# DRV8305.net
KiCad netlist of a schematic drawn in Altium Designer
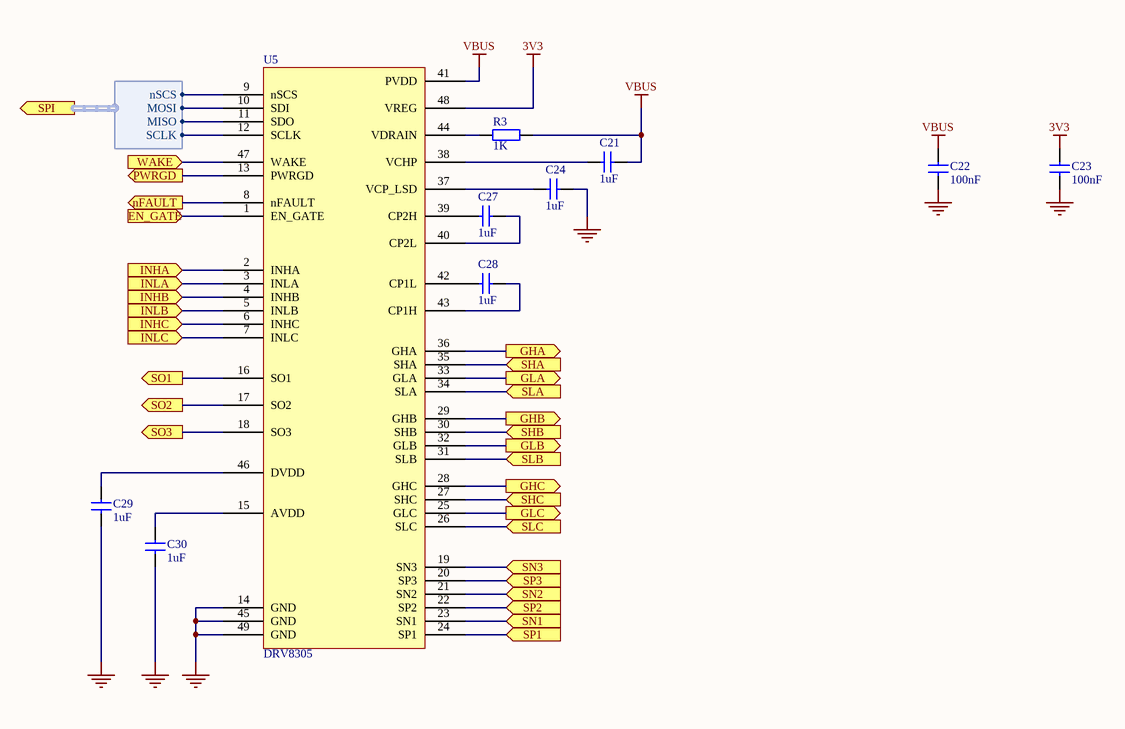
[diagram p0: DRV8305.SchDoc]

(export (version "E")
  (design (tool "Eeschema 10.0.6"))
  (components
    (comp (ref "C21")
      (value "1uF")
      (footprint "CAP0402(1005)_N")
      (description "Capacitor")
      (fields (field (name "PART") "cap_generic"))
      (libsource (lib "hitiqlib") (part "cap"))
    )
    (comp (ref "C22")
      (value "100nF")
      (footprint "CAP0402(1005)_N")
      (description "Capacitor")
      (fields (field (name "PART") "cap_generic"))
      (libsource (lib "hitiqlib") (part "cap"))
    )
    (comp (ref "C23")
      (value "100nF")
      (footprint "CAP0402(1005)_N")
      (description "Capacitor")
      (fields (field (name "PART") "cap_generic"))
      (libsource (lib "hitiqlib") (part "cap"))
    )
    (comp (ref "C24")
      (value "1uF")
      (footprint "CAP0402(1005)_N")
      (description "Capacitor")
      (fields (field (name "PART") "cap_generic"))
      (libsource (lib "hitiqlib") (part "cap"))
    )
    (comp (ref "C27")
      (value "1uF")
      (footprint "CAP0402(1005)_N")
      (description "Capacitor")
      (fields (field (name "PART") "cap_generic"))
      (libsource (lib "hitiqlib") (part "cap"))
    )
    (comp (ref "C28")
      (value "1uF")
      (footprint "CAP0402(1005)_N")
      (description "Capacitor")
      (fields (field (name "PART") "cap_generic"))
      (libsource (lib "hitiqlib") (part "cap"))
    )
    (comp (ref "C29")
      (value "1uF")
      (footprint "CAP0402(1005)_N")
      (description "Capacitor")
      (fields (field (name "PART") "cap_generic"))
      (libsource (lib "hitiqlib") (part "cap"))
    )
    (comp (ref "C30")
      (value "1uF")
      (footprint "CAP0402(1005)_N")
      (description "Capacitor")
      (fields (field (name "PART") "cap_generic"))
      (libsource (lib "hitiqlib") (part "cap"))
    )
    (comp (ref "R3")
      (value "1K")
      (footprint "RESC0603(1608)_N")
      (description "Resistor")
      (fields (field (name "PART") "res_0603"))
      (libsource (lib "hitiqlib") (part "Resistor"))
    )
    (comp (ref "U5")
      (value "DRV8305")
      (footprint "S-PQFP-G48")
      (fields (field (name "MANUFACTURER") "Texas Instruments"))
      (libsource (lib "hitiqlib") (part "DRV8305"))
    )
  )
  (nets
    (net (code "2") (name "/EN_GATE") (class "Default")
      (node (ref "U5") (pin "1") (pinfunction "EN_GATE_1") (pintype "passive"))
    )
    (net (code "3") (name "/GHA") (class "Default")
      (node (ref "U5") (pin "36") (pinfunction "GHA_36") (pintype "passive"))
    )
    (net (code "4") (name "/GHB") (class "Default")
      (node (ref "U5") (pin "29") (pinfunction "GHB_29") (pintype "passive"))
    )
    (net (code "5") (name "/GHC") (class "Default")
      (node (ref "U5") (pin "28") (pinfunction "GHC_28") (pintype "passive"))
    )
    (net (code "6") (name "/GLA") (class "Default")
      (node (ref "U5") (pin "33") (pinfunction "GLA_33") (pintype "passive"))
    )
    (net (code "7") (name "/GLB") (class "Default")
      (node (ref "U5") (pin "32") (pinfunction "GLB_32") (pintype "passive"))
    )
    (net (code "8") (name "/GLC") (class "Default")
      (node (ref "U5") (pin "25") (pinfunction "GLC_25") (pintype "passive"))
    )
    (net (code "9") (name "/INHA") (class "Default")
      (node (ref "U5") (pin "2") (pinfunction "INHA_2") (pintype "passive"))
    )
    (net (code "10") (name "/INHB") (class "Default")
      (node (ref "U5") (pin "4") (pinfunction "INHB_4") (pintype "passive"))
    )
    (net (code "11") (name "/INHC") (class "Default")
      (node (ref "U5") (pin "6") (pinfunction "INHC_6") (pintype "passive"))
    )
    (net (code "12") (name "/INLA") (class "Default")
      (node (ref "U5") (pin "3") (pinfunction "INLA_3") (pintype "passive"))
    )
    (net (code "13") (name "/INLB") (class "Default")
      (node (ref "U5") (pin "5") (pinfunction "INLB_5") (pintype "passive"))
    )
    (net (code "14") (name "/INLC") (class "Default")
      (node (ref "U5") (pin "7") (pinfunction "INLC_7") (pintype "passive"))
    )
    (net (code "15") (name "/MISO") (class "Default")
      (node (ref "U5") (pin "11") (pinfunction "SDO_11") (pintype "passive"))
    )
    (net (code "16") (name "/MOSI") (class "Default")
      (node (ref "U5") (pin "10") (pinfunction "SDI_10") (pintype "passive"))
    )
    (net (code "17") (name "/PWRGD") (class "Default")
      (node (ref "U5") (pin "13") (pinfunction "PWRGD_13") (pintype "passive"))
    )
    (net (code "18") (name "/SCLK") (class "Default")
      (node (ref "U5") (pin "12") (pinfunction "SCLK_12") (pintype "passive"))
    )
    (net (code "19") (name "/SHA") (class "Default")
      (node (ref "U5") (pin "35") (pinfunction "SHA_35") (pintype "passive"))
    )
    (net (code "20") (name "/SHB") (class "Default")
      (node (ref "U5") (pin "30") (pinfunction "SHB_30") (pintype "passive"))
    )
    (net (code "21") (name "/SHC") (class "Default")
      (node (ref "U5") (pin "27") (pinfunction "SHC_27") (pintype "passive"))
    )
    (net (code "22") (name "/SLA") (class "Default")
      (node (ref "U5") (pin "34") (pinfunction "SLA_34") (pintype "passive"))
    )
    (net (code "23") (name "/SLB") (class "Default")
      (node (ref "U5") (pin "31") (pinfunction "SLB_31") (pintype "passive"))
    )
    (net (code "24") (name "/SLC") (class "Default")
      (node (ref "U5") (pin "26") (pinfunction "SLC_26") (pintype "passive"))
    )
    (net (code "25") (name "/SN1") (class "Default")
      (node (ref "U5") (pin "23") (pinfunction "SN1_23") (pintype "passive"))
    )
    (net (code "26") (name "/SN2") (class "Default")
      (node (ref "U5") (pin "21") (pinfunction "SN2_21") (pintype "passive"))
    )
    (net (code "27") (name "/SN3") (class "Default")
      (node (ref "U5") (pin "19") (pinfunction "SN3_19") (pintype "passive"))
    )
    (net (code "28") (name "/SO1") (class "Default")
      (node (ref "U5") (pin "16") (pinfunction "SO1_16") (pintype "passive"))
    )
    (net (code "29") (name "/SO2") (class "Default")
      (node (ref "U5") (pin "17") (pinfunction "SO2_17") (pintype "passive"))
    )
    (net (code "30") (name "/SO3") (class "Default")
      (node (ref "U5") (pin "18") (pinfunction "SO3_18") (pintype "passive"))
    )
    (net (code "31") (name "/SP1") (class "Default")
      (node (ref "U5") (pin "24") (pinfunction "SP1_24") (pintype "passive"))
    )
    (net (code "32") (name "/SP2") (class "Default")
      (node (ref "U5") (pin "22") (pinfunction "SP2_22") (pintype "passive"))
    )
    (net (code "33") (name "/SP3") (class "Default")
      (node (ref "U5") (pin "20") (pinfunction "SP3_20") (pintype "passive"))
    )
    (net (code "34") (name "/WAKE") (class "Default")
      (node (ref "U5") (pin "47") (pinfunction "WAKE_47") (pintype "passive"))
    )
    (net (code "35") (name "/nFAULT") (class "Default")
      (node (ref "U5") (pin "8") (pinfunction "nFAULT_8") (pintype "passive"))
    )
    (net (code "36") (name "/nSCS") (class "Default")
      (node (ref "U5") (pin "9") (pinfunction "nSCS_9") (pintype "passive"))
    )
    (net (code "38") (name "3V3") (class "Default")
      (node (ref "C23") (pin "2") (pintype "passive"))
      (node (ref "U5") (pin "48") (pinfunction "VREG_48") (pintype "passive"))
    )
    (net (code "39") (name "GND") (class "Default")
      (node (ref "C22") (pin "1") (pintype "passive"))
      (node (ref "C23") (pin "1") (pintype "passive"))
      (node (ref "C24") (pin "1") (pintype "passive"))
      (node (ref "C29") (pin "1") (pintype "passive"))
      (node (ref "C30") (pin "1") (pintype "passive"))
      (node (ref "U5") (pin "14") (pinfunction "GND_14") (pintype "passive"))
      (node (ref "U5") (pin "45") (pinfunction "GND_45") (pintype "passive"))
      (node (ref "U5") (pin "49") (pinfunction "GND_49") (pintype "passive"))
    )
    (net (code "40") (name "Net-(U5-AVDD)") (class "Default")
      (node (ref "C30") (pin "2") (pintype "passive"))
      (node (ref "U5") (pin "15") (pinfunction "AVDD_15") (pintype "passive"))
    )
    (net (code "41") (name "Net-(U5-CP1H)") (class "Default")
      (node (ref "C28") (pin "1") (pintype "passive"))
      (node (ref "U5") (pin "43") (pinfunction "CP1H_43") (pintype "passive"))
    )
    (net (code "42") (name "Net-(U5-CP1L)") (class "Default")
      (node (ref "C28") (pin "2") (pintype "passive"))
      (node (ref "U5") (pin "42") (pinfunction "CP1L_42") (pintype "passive"))
    )
    (net (code "43") (name "Net-(U5-CP2H)") (class "Default")
      (node (ref "C27") (pin "2") (pintype "passive"))
      (node (ref "U5") (pin "39") (pinfunction "CP2H_39") (pintype "passive"))
    )
    (net (code "44") (name "Net-(U5-CP2L)") (class "Default")
      (node (ref "C27") (pin "1") (pintype "passive"))
      (node (ref "U5") (pin "40") (pinfunction "CP2L_40") (pintype "passive"))
    )
    (net (code "45") (name "Net-(U5-DVDD)") (class "Default")
      (node (ref "C29") (pin "2") (pintype "passive"))
      (node (ref "U5") (pin "46") (pinfunction "DVDD_46") (pintype "passive"))
    )
    (net (code "46") (name "Net-(U5-VCHP)") (class "Default")
      (node (ref "C21") (pin "2") (pintype "passive"))
      (node (ref "U5") (pin "38") (pinfunction "VCHP_38") (pintype "passive"))
    )
    (net (code "47") (name "Net-(U5-VCP_LSD)") (class "Default")
      (node (ref "C24") (pin "2") (pintype "passive"))
      (node (ref "U5") (pin "37") (pinfunction "VCP_LSD_37") (pintype "passive"))
    )
    (net (code "48") (name "Net-(U5-VDRAIN)") (class "Default")
      (node (ref "R3") (pin "1") (pintype "passive"))
      (node (ref "U5") (pin "44") (pinfunction "VDRAIN_44") (pintype "passive"))
    )
    (net (code "49") (name "VBUS") (class "Default")
      (node (ref "C21") (pin "1") (pintype "passive"))
      (node (ref "C22") (pin "2") (pintype "passive"))
      (node (ref "R3") (pin "2") (pintype "passive"))
      (node (ref "U5") (pin "41") (pinfunction "PVDD_41") (pintype "passive"))
    )
  )
)
